# SparkFun-ESP8266-WiFi-Shield.net
KiCad netlist of a schematic drawn in EAGLE
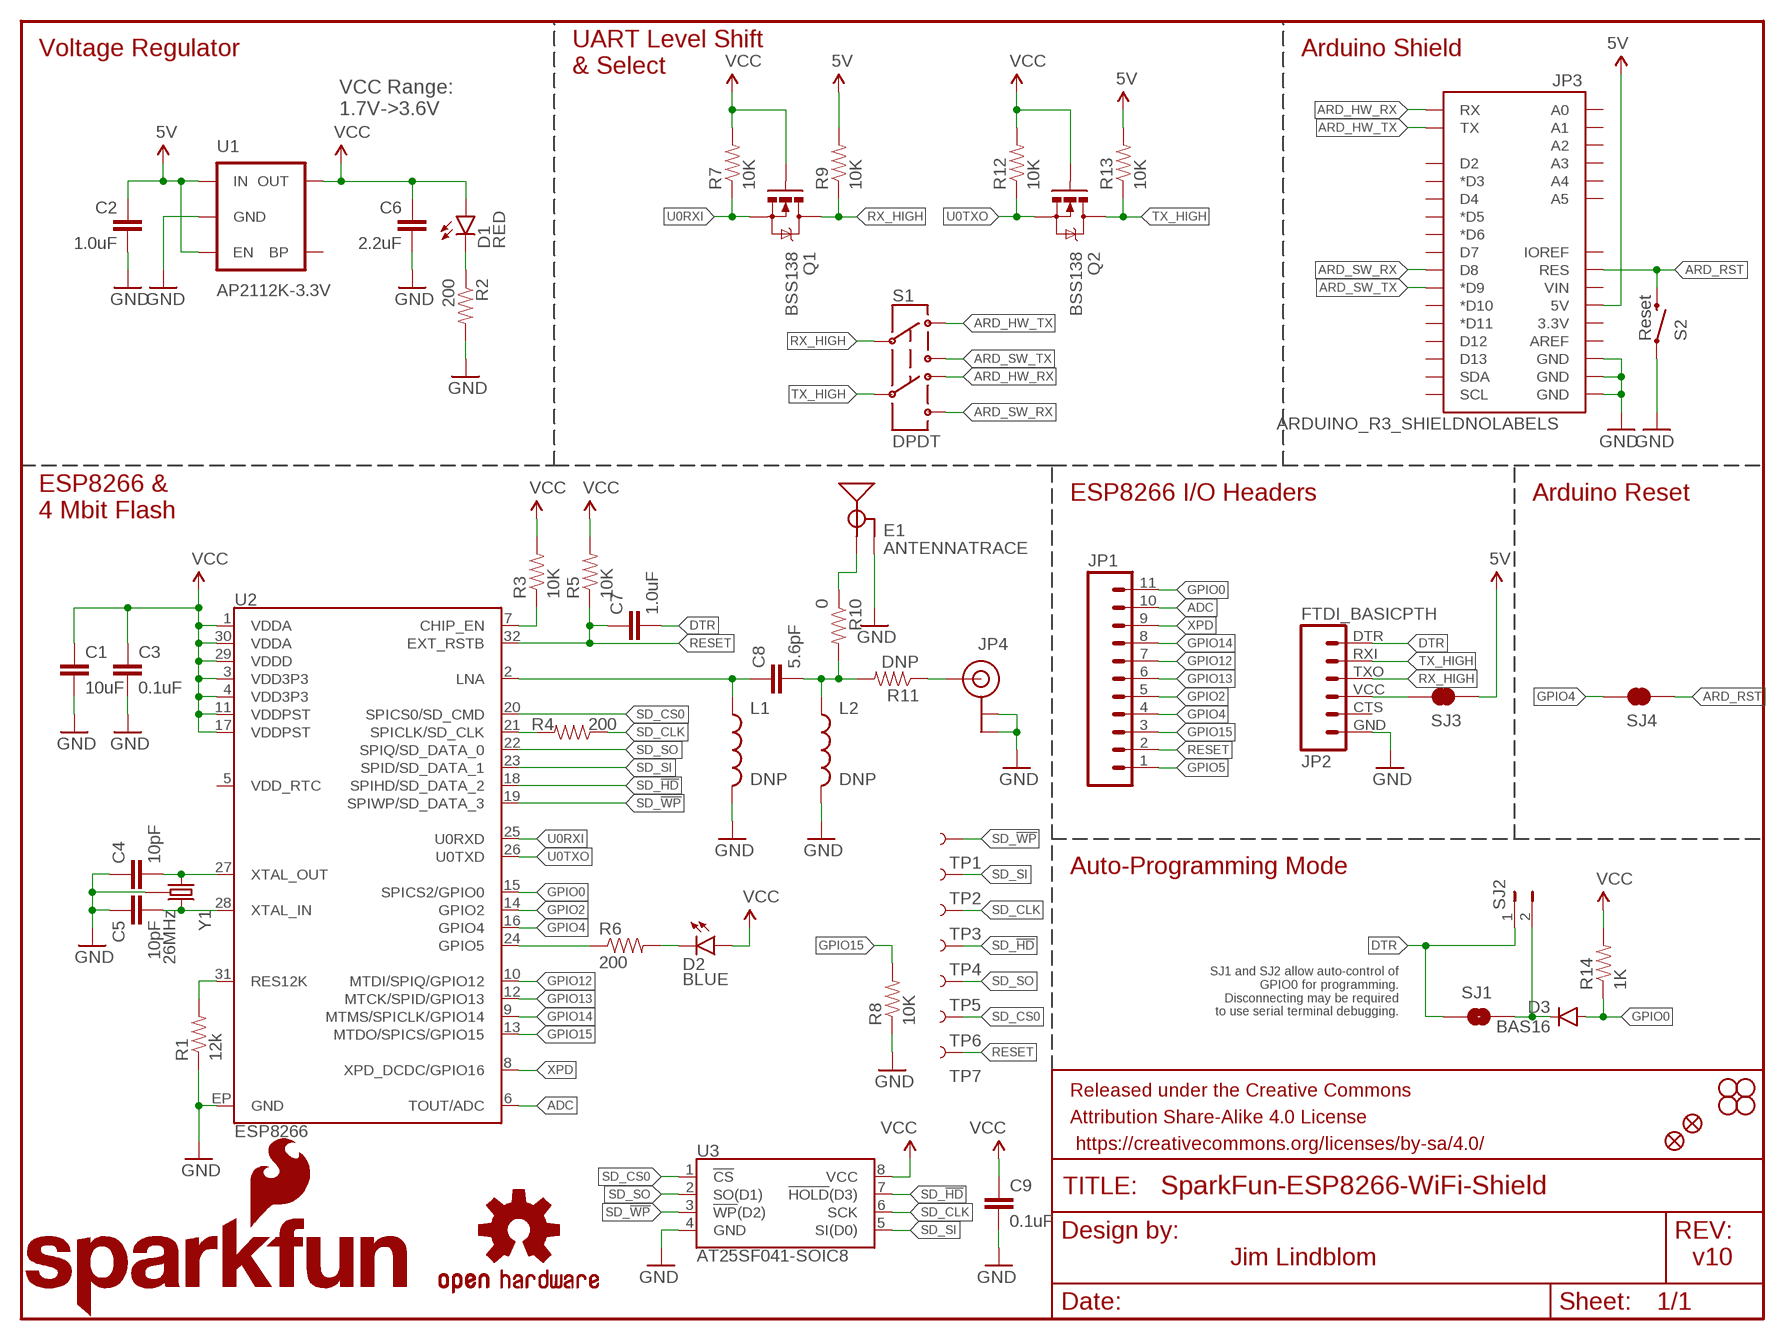
[diagram p0: schematic, sheet 1]

(export (version "E")
  (design (tool "Eeschema 10.0.6"))
  (components
    (comp (ref "C1")
      (value "10uF")
      (footprint "eagle-import:0603-CAP")
      (libsource (lib "eagle-import") (part "10UF-6.3V-20%(0603)"))
    )
    (comp (ref "C2")
      (value "1.0uF")
      (footprint "eagle-import:0805")
      (libsource (lib "eagle-import") (part "1.0UF-25V-+80/-20(0805)"))
    )
    (comp (ref "C3")
      (value "0.1uF")
      (footprint "eagle-import:0603-CAP")
      (libsource (lib "eagle-import") (part "0.1UF-25V(+80/-20%)(0603)"))
    )
    (comp (ref "C4")
      (value "10pF")
      (footprint "eagle-import:0603-CAP")
      (libsource (lib "eagle-import") (part "10PF-50V-5%(0603)"))
    )
    (comp (ref "C5")
      (value "10pF")
      (footprint "eagle-import:0603-CAP")
      (libsource (lib "eagle-import") (part "10PF-50V-5%(0603)"))
    )
    (comp (ref "C6")
      (value "2.2uF")
      (footprint "eagle-import:0603-CAP")
      (libsource (lib "eagle-import") (part "2.2UF-10V-20%(0603)"))
    )
    (comp (ref "C7")
      (value "1.0uF")
      (footprint "eagle-import:0603-CAP")
      (libsource (lib "eagle-import") (part "1.0UF-16V-10%(0603)"))
    )
    (comp (ref "C8")
      (value "5.6pF")
      (footprint "eagle-import:0603-CAP")
      (libsource (lib "eagle-import") (part "CAP0603-CAP"))
    )
    (comp (ref "C9")
      (value "0.1uF")
      (footprint "eagle-import:0603-CAP")
      (libsource (lib "eagle-import") (part "0.1UF-25V(+80/-20%)(0603)"))
    )
    (comp (ref "D1")
      (value "RED")
      (footprint "eagle-import:LED-0603")
      (libsource (lib "eagle-import") (part "LED-RED0603"))
    )
    (comp (ref "D2")
      (value "BLUE")
      (footprint "eagle-import:LED-0603")
      (libsource (lib "eagle-import") (part "LED-BLUE0603"))
    )
    (comp (ref "D3")
      (value "BAS16")
      (footprint "eagle-import:SOD-323")
      (libsource (lib "eagle-import") (part "DIODEBAS16"))
    )
    (comp (ref "E1")
      (value "ANTENNATRACE")
      (footprint "eagle-import:TRACE_ANTENNA_2.4GHZ_25.7MM")
      (libsource (lib "eagle-import") (part "ANTENNATRACE"))
    )
    (comp (ref "FID1")
      (value "FIDUCIAL1X2")
      (footprint "eagle-import:FIDUCIAL-1X2")
      (libsource (lib "eagle-import") (part "FIDUCIAL1X2"))
    )
    (comp (ref "FID2")
      (value "FIDUCIAL1X2")
      (footprint "eagle-import:FIDUCIAL-1X2")
      (libsource (lib "eagle-import") (part "FIDUCIAL1X2"))
    )
    (comp (ref "FRAME1")
      (value "FRAME-LETTER")
      (footprint "eagle-import:CREATIVE_COMMONS")
      (fields (field (name "DESIGNER") "Jim Lindblom"))
      (libsource (lib "eagle-import") (part "FRAME-LETTER"))
    )
    (comp (ref "JP1")
      (value "M11PTH")
      (footprint "eagle-import:1X11")
      (libsource (lib "eagle-import") (part "M11PTH"))
    )
    (comp (ref "JP2")
      (value "FTDI_BASICPTH")
      (footprint "eagle-import:FTDI_BASIC")
      (libsource (lib "eagle-import") (part "FTDI_BASICPTH"))
    )
    (comp (ref "JP3")
      (value "ARDUINO_R3_SHIELDNOLABELS")
      (footprint "eagle-import:UNO_R3_SHIELD_NOLABELS")
      (libsource (lib "eagle-import") (part "ARDUINO_R3_SHIELDNOLABELS"))
    )
    (comp (ref "JP4")
      (value "U.FL")
      (footprint "eagle-import:U.FL")
      (libsource (lib "eagle-import") (part "U.FL"))
    )
    (comp (ref "L1")
      (value "DNP")
      (footprint "eagle-import:0603")
      (libsource (lib "eagle-import") (part "INDUCTOR0603"))
    )
    (comp (ref "L2")
      (value "DNP")
      (footprint "eagle-import:0603")
      (libsource (lib "eagle-import") (part "INDUCTOR0603"))
    )
    (comp (ref "LOGO1")
      (value "SFE_LOGO_NAME_FLAME.2_INCH")
      (footprint "eagle-import:SFE_LOGO_NAME_FLAME_.2")
      (libsource (lib "eagle-import") (part "SFE_LOGO_NAME_FLAME.2_INCH"))
    )
    (comp (ref "LOGO2")
      (value "OSHW-LOGOM")
      (footprint "eagle-import:OSHW-LOGO-M")
      (libsource (lib "eagle-import") (part "OSHW-LOGOM"))
    )
    (comp (ref "Q1")
      (value "BSS138")
      (footprint "eagle-import:SOT23-3")
      (libsource (lib "eagle-import") (part "MOSFET-NCHANNELBSS138"))
    )
    (comp (ref "Q2")
      (value "BSS138")
      (footprint "eagle-import:SOT23-3")
      (libsource (lib "eagle-import") (part "MOSFET-NCHANNELBSS138"))
    )
    (comp (ref "R1")
      (value "12k")
      (footprint "eagle-import:0603-RES")
      (libsource (lib "eagle-import") (part "12KOHM-1/10W-1%(0603)"))
    )
    (comp (ref "R2")
      (value "200")
      (footprint "eagle-import:0603-RES")
      (libsource (lib "eagle-import") (part "200OHM1/10W1%(0603)"))
    )
    (comp (ref "R3")
      (value "10K")
      (footprint "eagle-import:0603-RES")
      (libsource (lib "eagle-import") (part "10KOHM1/10W1%(0603)0603"))
    )
    (comp (ref "R4")
      (value "200")
      (footprint "eagle-import:0603-RES")
      (libsource (lib "eagle-import") (part "200OHM1/10W1%(0603)"))
    )
    (comp (ref "R5")
      (value "10K")
      (footprint "eagle-import:0603-RES")
      (libsource (lib "eagle-import") (part "10KOHM1/10W1%(0603)0603"))
    )
    (comp (ref "R6")
      (value "200")
      (footprint "eagle-import:0603-RES")
      (libsource (lib "eagle-import") (part "200OHM1/10W1%(0603)"))
    )
    (comp (ref "R7")
      (value "10K")
      (footprint "eagle-import:0603-RES")
      (libsource (lib "eagle-import") (part "10KOHM1/10W1%(0603)0603"))
    )
    (comp (ref "R8")
      (value "10K")
      (footprint "eagle-import:0603-RES")
      (libsource (lib "eagle-import") (part "10KOHM1/10W1%(0603)0603"))
    )
    (comp (ref "R9")
      (value "10K")
      (footprint "eagle-import:0603-RES")
      (libsource (lib "eagle-import") (part "10KOHM1/10W1%(0603)0603"))
    )
    (comp (ref "R10")
      (value "0")
      (footprint "eagle-import:0603")
      (libsource (lib "eagle-import") (part "0OHM1/10W5%(0603)"))
    )
    (comp (ref "R11")
      (value "DNP")
      (footprint "eagle-import:0603-RES")
      (libsource (lib "eagle-import") (part "RESISTOR0603-RES"))
    )
    (comp (ref "R12")
      (value "10K")
      (footprint "eagle-import:0603-RES")
      (libsource (lib "eagle-import") (part "10KOHM1/10W1%(0603)0603"))
    )
    (comp (ref "R13")
      (value "10K")
      (footprint "eagle-import:0603-RES")
      (libsource (lib "eagle-import") (part "10KOHM1/10W1%(0603)0603"))
    )
    (comp (ref "R14")
      (value "1K")
      (footprint "eagle-import:0603-RES")
      (libsource (lib "eagle-import") (part "1KOHM1/10W1%(0603)"))
    )
    (comp (ref "S1")
      (value "DPDT")
      (footprint "eagle-import:AYZ0202")
      (libsource (lib "eagle-import") (part "SWITCH-DPDTAYZ0202"))
    )
    (comp (ref "S2")
      (value "Reset")
      (footprint "eagle-import:TACTILE-SWITCH-SMD")
      (libsource (lib "eagle-import") (part "SWITCH-MOMENTARY-2SMD"))
    )
    (comp (ref "SJ1")
      (value "JUMPER-PAD-2-NO")
      (footprint "eagle-import:PAD-JUMPER-2-NO_NO_SILK")
      (libsource (lib "eagle-import") (part "JUMPER-PAD-2-NO"))
    )
    (comp (ref "SJ2")
      (value "JUMPER-PTH-2-NO")
      (footprint "eagle-import:PTH-JUMPER-2-NO_NO_SILK")
      (libsource (lib "eagle-import") (part "JUMPER-PTH-2-NO"))
    )
    (comp (ref "SJ3")
      (value "JUMPER-PAD-2-NC_BY_TRACE")
      (footprint "eagle-import:PAD-JUMPER-2-NC_BY_TRACE_YES_SILK")
      (libsource (lib "eagle-import") (part "JUMPER-PAD-2-NC_BY_TRACE"))
    )
    (comp (ref "SJ4")
      (value "JUMPER-PAD-2-NC_BY_TRACE")
      (footprint "eagle-import:PAD-JUMPER-2-NC_BY_TRACE_YES_SILK")
      (libsource (lib "eagle-import") (part "JUMPER-PAD-2-NC_BY_TRACE"))
    )
    (comp (ref "STANDOFF1")
      (value "STAND-OFF")
      (footprint "eagle-import:STAND-OFF")
      (libsource (lib "eagle-import") (part "STAND-OFF"))
    )
    (comp (ref "STANDOFF2")
      (value "STAND-OFF")
      (footprint "eagle-import:STAND-OFF")
      (libsource (lib "eagle-import") (part "STAND-OFF"))
    )
    (comp (ref "STANDOFF3")
      (value "STAND-OFF")
      (footprint "eagle-import:STAND-OFF")
      (libsource (lib "eagle-import") (part "STAND-OFF"))
    )
    (comp (ref "STANDOFF4")
      (value "STAND-OFF")
      (footprint "eagle-import:STAND-OFF")
      (libsource (lib "eagle-import") (part "STAND-OFF"))
    )
    (comp (ref "TP1")
      (value "TEST-POINT3X5")
      (footprint "eagle-import:PAD.03X.05")
      (libsource (lib "eagle-import") (part "TEST-POINT3X5"))
    )
    (comp (ref "TP2")
      (value "TEST-POINT3X5")
      (footprint "eagle-import:PAD.03X.05")
      (libsource (lib "eagle-import") (part "TEST-POINT3X5"))
    )
    (comp (ref "TP3")
      (value "TEST-POINT3X5")
      (footprint "eagle-import:PAD.03X.05")
      (libsource (lib "eagle-import") (part "TEST-POINT3X5"))
    )
    (comp (ref "TP4")
      (value "TEST-POINT3X5")
      (footprint "eagle-import:PAD.03X.05")
      (libsource (lib "eagle-import") (part "TEST-POINT3X5"))
    )
    (comp (ref "TP5")
      (value "TEST-POINT3X5")
      (footprint "eagle-import:PAD.03X.05")
      (libsource (lib "eagle-import") (part "TEST-POINT3X5"))
    )
    (comp (ref "TP6")
      (value "TEST-POINT3X5")
      (footprint "eagle-import:PAD.03X.05")
      (libsource (lib "eagle-import") (part "TEST-POINT3X5"))
    )
    (comp (ref "TP7")
      (value "TEST-POINT3X5")
      (footprint "eagle-import:PAD.03X.05")
      (libsource (lib "eagle-import") (part "TEST-POINT3X5"))
    )
    (comp (ref "U1")
      (value "AP2112K-3.3V")
      (footprint "eagle-import:SOT23-5")
      (libsource (lib "eagle-import") (part "V_REG_LDOSMD"))
    )
    (comp (ref "U2")
      (value "ESP8266")
      (footprint "eagle-import:QFN32")
      (libsource (lib "eagle-import") (part "ESP8266"))
    )
    (comp (ref "U3")
      (value "AT25SF041-SOIC8")
      (footprint "eagle-import:SO08")
      (libsource (lib "eagle-import") (part "AT25SF041-SOIC8"))
    )
    (comp (ref "Y1")
      (value "26MHz")
      (footprint "eagle-import:CRYSTAL-SMD-3.2X2.5")
      (libsource (lib "eagle-import") (part "CRYSTAL-GROUNDED3.2X2.5"))
    )
  )
  (nets
    (net (code "1") (name "/SD_~{HD}") (class "Default")
      (node (ref "TP4") (pin "P$1") (pinfunction "1_P$1") (pintype "bidirectional"))
      (node (ref "U2") (pin "18") (pinfunction "SPIHD/SD_DATA_2_18") (pintype "bidirectional"))
      (node (ref "U3") (pin "7") (pinfunction "~{HOLD}(D3)_7") (pintype "bidirectional"))
    )
    (net (code "2") (name "/SD_~{WP}") (class "Default")
      (node (ref "TP1") (pin "P$1") (pinfunction "1_P$1") (pintype "bidirectional"))
      (node (ref "U2") (pin "19") (pinfunction "SPIWP/SD_DATA_3_19") (pintype "bidirectional"))
      (node (ref "U3") (pin "3") (pinfunction "~{WP}(D2)_3") (pintype "bidirectional"))
    )
    (net (code "3") (name "5V") (class "Default")
      (node (ref "C2") (pin "1") (pinfunction "1_1") (pintype "passive"))
      (node (ref "JP3") (pin "5V") (pinfunction "5V_5V") (pintype "bidirectional"))
      (node (ref "R13") (pin "2") (pinfunction "2_2") (pintype "passive"))
      (node (ref "R9") (pin "2") (pinfunction "2_2") (pintype "passive"))
      (node (ref "SJ3") (pin "1") (pinfunction "1_1") (pintype "passive"))
      (node (ref "U1") (pin "1") (pinfunction "IN_1") (pintype "input"))
      (node (ref "U1") (pin "3") (pinfunction "EN_3") (pintype "input"))
    )
    (net (code "4") (name "ADC") (class "Default")
      (node (ref "JP1") (pin "10") (pinfunction "10_10") (pintype "passive"))
      (node (ref "U2") (pin "6") (pinfunction "TOUT/ADC_6") (pintype "bidirectional"))
    )
    (net (code "5") (name "ARD_HW_RX") (class "Default")
      (node (ref "JP3") (pin "RX") (pinfunction "RX_RX") (pintype "bidirectional"))
      (node (ref "S1") (pin "4") (pinfunction "4_4") (pintype "bidirectional"))
    )
    (net (code "6") (name "ARD_HW_TX") (class "Default")
      (node (ref "JP3") (pin "TX") (pinfunction "TX_TX") (pintype "bidirectional"))
      (node (ref "S1") (pin "1") (pinfunction "1_1") (pintype "bidirectional"))
    )
    (net (code "7") (name "ARD_RST") (class "Default")
      (node (ref "JP3") (pin "RES") (pinfunction "RES_RES") (pintype "bidirectional"))
      (node (ref "S2") (pin "3") (pinfunction "2_3") (pintype "passive"))
      (node (ref "SJ4") (pin "1") (pinfunction "1_1") (pintype "passive"))
    )
    (net (code "8") (name "ARD_SW_RX") (class "Default")
      (node (ref "JP3") (pin "D8") (pinfunction "D8_D8") (pintype "bidirectional"))
      (node (ref "S1") (pin "6") (pinfunction "6_6") (pintype "bidirectional"))
    )
    (net (code "9") (name "ARD_SW_TX") (class "Default")
      (node (ref "JP3") (pin "D9") (pinfunction "*D9_D9") (pintype "bidirectional"))
      (node (ref "S1") (pin "3") (pinfunction "3_3") (pintype "bidirectional"))
    )
    (net (code "10") (name "DTR") (class "Default")
      (node (ref "C7") (pin "2") (pinfunction "2_2") (pintype "passive"))
      (node (ref "JP2") (pin "DTR") (pinfunction "1_DTR") (pintype "passive"))
      (node (ref "SJ1") (pin "1") (pinfunction "1_1") (pintype "passive"))
      (node (ref "SJ2") (pin "1") (pinfunction "1_1") (pintype "passive"))
    )
    (net (code "11") (name "GND") (class "Default")
      (node (ref "C1") (pin "2") (pinfunction "2_2") (pintype "passive"))
      (node (ref "C2") (pin "2") (pinfunction "2_2") (pintype "passive"))
      (node (ref "C3") (pin "2") (pinfunction "2_2") (pintype "passive"))
      (node (ref "C4") (pin "1") (pinfunction "1_1") (pintype "passive"))
      (node (ref "C5") (pin "1") (pinfunction "1_1") (pintype "passive"))
      (node (ref "C6") (pin "2") (pinfunction "2_2") (pintype "passive"))
      (node (ref "C9") (pin "2") (pinfunction "2_2") (pintype "passive"))
      (node (ref "E1") (pin "GND") (pinfunction "GND_GND") (pintype "bidirectional"))
      (node (ref "E1") (pin "GND2") (pinfunction "GND_GND2") (pintype "bidirectional"))
      (node (ref "JP2") (pin "GND") (pinfunction "6_GND") (pintype "passive"))
      (node (ref "JP3") (pin "GND@0") (pinfunction "GND_GND@0") (pintype "bidirectional"))
      (node (ref "JP3") (pin "GND@1") (pinfunction "GND_GND@1") (pintype "bidirectional"))
      (node (ref "JP3") (pin "GND@2") (pinfunction "GND_GND@2") (pintype "bidirectional"))
      (node (ref "JP4") (pin "P$1") (pinfunction "GND_P$1") (pintype "bidirectional"))
      (node (ref "JP4") (pin "P$2") (pinfunction "GND_P$2") (pintype "bidirectional"))
      (node (ref "L1") (pin "2") (pinfunction "2_2") (pintype "passive"))
      (node (ref "L2") (pin "2") (pinfunction "2_2") (pintype "passive"))
      (node (ref "R1") (pin "1") (pinfunction "1_1") (pintype "passive"))
      (node (ref "R2") (pin "2") (pinfunction "2_2") (pintype "passive"))
      (node (ref "R8") (pin "1") (pinfunction "1_1") (pintype "passive"))
      (node (ref "S2") (pin "1") (pinfunction "1_1") (pintype "passive"))
      (node (ref "U1") (pin "2") (pinfunction "GND_2") (pintype "input"))
      (node (ref "U2") (pin "EP") (pinfunction "GND_EP") (pintype "bidirectional"))
      (node (ref "U3") (pin "4") (pinfunction "GND_4") (pintype "bidirectional"))
      (node (ref "Y1") (pin "2") (pinfunction "GND_2") (pintype "passive"))
      (node (ref "Y1") (pin "4") (pinfunction "GND_4") (pintype "passive"))
    )
    (net (code "12") (name "GPIO0") (class "Default")
      (node (ref "D3") (pin "A") (pinfunction "A_A") (pintype "passive"))
      (node (ref "JP1") (pin "11") (pinfunction "11_11") (pintype "passive"))
      (node (ref "R14") (pin "1") (pinfunction "1_1") (pintype "passive"))
      (node (ref "U2") (pin "15") (pinfunction "SPICS2/GPIO0_15") (pintype "bidirectional"))
    )
    (net (code "13") (name "GPIO2") (class "Default")
      (node (ref "JP1") (pin "5") (pinfunction "5_5") (pintype "passive"))
      (node (ref "U2") (pin "14") (pinfunction "GPIO2_14") (pintype "bidirectional"))
    )
    (net (code "14") (name "GPIO4") (class "Default")
      (node (ref "JP1") (pin "4") (pinfunction "4_4") (pintype "passive"))
      (node (ref "SJ4") (pin "2") (pinfunction "2_2") (pintype "passive"))
      (node (ref "U2") (pin "16") (pinfunction "GPIO4_16") (pintype "bidirectional"))
    )
    (net (code "15") (name "GPIO5") (class "Default")
      (node (ref "JP1") (pin "1") (pinfunction "1_1") (pintype "passive"))
      (node (ref "R6") (pin "1") (pinfunction "1_1") (pintype "passive"))
      (node (ref "U2") (pin "24") (pinfunction "GPIO5_24") (pintype "bidirectional"))
    )
    (net (code "16") (name "GPIO12") (class "Default")
      (node (ref "JP1") (pin "7") (pinfunction "7_7") (pintype "passive"))
      (node (ref "U2") (pin "10") (pinfunction "MTDI/SPIQ/GPIO12_10") (pintype "bidirectional"))
    )
    (net (code "17") (name "GPIO13") (class "Default")
      (node (ref "JP1") (pin "6") (pinfunction "6_6") (pintype "passive"))
      (node (ref "U2") (pin "12") (pinfunction "MTCK/SPID/GPIO13_12") (pintype "bidirectional"))
    )
    (net (code "18") (name "GPIO14") (class "Default")
      (node (ref "JP1") (pin "8") (pinfunction "8_8") (pintype "passive"))
      (node (ref "U2") (pin "9") (pinfunction "MTMS/SPICLK/GPIO14_9") (pintype "bidirectional"))
    )
    (net (code "19") (name "GPIO15") (class "Default")
      (node (ref "JP1") (pin "3") (pinfunction "3_3") (pintype "passive"))
      (node (ref "R8") (pin "2") (pinfunction "2_2") (pintype "passive"))
      (node (ref "U2") (pin "13") (pinfunction "MTDO/SPICS/GPIO15_13") (pintype "bidirectional"))
    )
    (net (code "20") (name "Net-(C8-Pad2)") (class "Default")
      (node (ref "C8") (pin "2") (pinfunction "2_2") (pintype "passive"))
      (node (ref "L2") (pin "1") (pinfunction "1_1") (pintype "passive"))
      (node (ref "R10") (pin "2") (pinfunction "2_2") (pintype "passive"))
      (node (ref "R11") (pin "2") (pinfunction "2_2") (pintype "passive"))
    )
    (net (code "21") (name "Net-(D1-PadC)") (class "Default")
      (node (ref "D1") (pin "C") (pinfunction "C_C") (pintype "passive"))
      (node (ref "R2") (pin "1") (pinfunction "1_1") (pintype "passive"))
    )
    (net (code "22") (name "Net-(D2-PadC)") (class "Default")
      (node (ref "D2") (pin "C") (pinfunction "C_C") (pintype "passive"))
      (node (ref "R6") (pin "2") (pinfunction "2_2") (pintype "passive"))
    )
    (net (code "23") (name "Net-(D3-PadC)") (class "Default")
      (node (ref "D3") (pin "C") (pinfunction "C_C") (pintype "passive"))
      (node (ref "SJ1") (pin "2") (pinfunction "2_2") (pintype "passive"))
      (node (ref "SJ2") (pin "2") (pinfunction "2_2") (pintype "passive"))
    )
    (net (code "24") (name "Net-(E1-SIGNAL)") (class "Default")
      (node (ref "E1") (pin "ANT") (pinfunction "SIGNAL_ANT") (pintype "bidirectional"))
      (node (ref "R10") (pin "1") (pinfunction "1_1") (pintype "passive"))
    )
    (net (code "25") (name "Net-(JP2-4)") (class "Default")
      (node (ref "JP2") (pin "VCC") (pinfunction "4_VCC") (pintype "passive"))
      (node (ref "SJ3") (pin "2") (pinfunction "2_2") (pintype "passive"))
    )
    (net (code "26") (name "Net-(JP4-SIGNAL)") (class "Default")
      (node (ref "JP4") (pin "P$3") (pinfunction "SIGNAL_P$3") (pintype "bidirectional"))
      (node (ref "R11") (pin "1") (pinfunction "1_1") (pintype "passive"))
    )
    (net (code "27") (name "Net-(U2-CHIP_EN)") (class "Default")
      (node (ref "R3") (pin "1") (pinfunction "1_1") (pintype "passive"))
      (node (ref "U2") (pin "7") (pinfunction "CHIP_EN_7") (pintype "bidirectional"))
    )
    (net (code "28") (name "Net-(U2-LNA)") (class "Default")
      (node (ref "C8") (pin "1") (pinfunction "1_1") (pintype "passive"))
      (node (ref "L1") (pin "1") (pinfunction "1_1") (pintype "passive"))
      (node (ref "U2") (pin "2") (pinfunction "LNA_2") (pintype "bidirectional"))
    )
    (net (code "29") (name "Net-(U2-RES12K)") (class "Default")
      (node (ref "R1") (pin "2") (pinfunction "2_2") (pintype "passive"))
      (node (ref "U2") (pin "31") (pinfunction "RES12K_31") (pintype "bidirectional"))
    )
    (net (code "30") (name "Net-(U2-SPICLK{slash}SD_CLK)") (class "Default")
      (node (ref "R4") (pin "2") (pinfunction "2_2") (pintype "passive"))
      (node (ref "U2") (pin "21") (pinfunction "SPICLK/SD_CLK_21") (pintype "bidirectional"))
    )
    (net (code "31") (name "Net-(U2-XTAL_IN)") (class "Default")
      (node (ref "C5") (pin "2") (pinfunction "2_2") (pintype "passive"))
      (node (ref "U2") (pin "28") (pinfunction "XTAL_IN_28") (pintype "bidirectional"))
      (node (ref "Y1") (pin "3") (pinfunction "2_3") (pintype "passive"))
    )
    (net (code "32") (name "Net-(U2-XTAL_OUT)") (class "Default")
      (node (ref "C4") (pin "2") (pinfunction "2_2") (pintype "passive"))
      (node (ref "U2") (pin "27") (pinfunction "XTAL_OUT_27") (pintype "bidirectional"))
      (node (ref "Y1") (pin "1") (pinfunction "1_1") (pintype "passive"))
    )
    (net (code "33") (name "RESET") (class "Default")
      (node (ref "C7") (pin "1") (pinfunction "1_1") (pintype "passive"))
      (node (ref "JP1") (pin "2") (pinfunction "2_2") (pintype "passive"))
      (node (ref "R5") (pin "1") (pinfunction "1_1") (pintype "passive"))
      (node (ref "TP7") (pin "P$1") (pinfunction "1_P$1") (pintype "bidirectional"))
      (node (ref "U2") (pin "32") (pinfunction "EXT_RSTB_32") (pintype "bidirectional"))
    )
    (net (code "34") (name "RX_HIGH") (class "Default")
      (node (ref "JP2") (pin "TXO") (pinfunction "3_TXO") (pintype "passive"))
      (node (ref "Q1") (pin "3") (pinfunction "D_3") (pintype "passive"))
      (node (ref "R9") (pin "1") (pinfunction "1_1") (pintype "passive"))
      (node (ref "S1") (pin "2") (pinfunction "2_2") (pintype "bidirectional"))
    )
    (net (code "35") (name "SD_CLK") (class "Default")
      (node (ref "R4") (pin "1") (pinfunction "1_1") (pintype "passive"))
      (node (ref "TP3") (pin "P$1") (pinfunction "1_P$1") (pintype "bidirectional"))
      (node (ref "U3") (pin "6") (pinfunction "SCK_6") (pintype "bidirectional"))
    )
    (net (code "36") (name "SD_CS0") (class "Default")
      (node (ref "TP6") (pin "P$1") (pinfunction "1_P$1") (pintype "bidirectional"))
      (node (ref "U2") (pin "20") (pinfunction "SPICS0/SD_CMD_20") (pintype "bidirectional"))
      (node (ref "U3") (pin "1") (pinfunction "~{CS}_1") (pintype "bidirectional"))
    )
    (net (code "37") (name "SD_SI") (class "Default")
      (node (ref "TP2") (pin "P$1") (pinfunction "1_P$1") (pintype "bidirectional"))
      (node (ref "U2") (pin "23") (pinfunction "SPID/SD_DATA_1_23") (pintype "bidirectional"))
      (node (ref "U3") (pin "5") (pinfunction "SI(D0)_5") (pintype "bidirectional"))
    )
    (net (code "38") (name "SD_SO") (class "Default")
      (node (ref "TP5") (pin "P$1") (pinfunction "1_P$1") (pintype "bidirectional"))
      (node (ref "U2") (pin "22") (pinfunction "SPIQ/SD_DATA_0_22") (pintype "bidirectional"))
      (node (ref "U3") (pin "2") (pinfunction "SO(D1)_2") (pintype "bidirectional"))
    )
    (net (code "39") (name "TX_HIGH") (class "Default")
      (node (ref "JP2") (pin "RXI") (pinfunction "2_RXI") (pintype "passive"))
      (node (ref "Q2") (pin "3") (pinfunction "D_3") (pintype "passive"))
      (node (ref "R13") (pin "1") (pinfunction "1_1") (pintype "passive"))
      (node (ref "S1") (pin "5") (pinfunction "5_5") (pintype "bidirectional"))
    )
    (net (code "40") (name "U0RXI") (class "Default")
      (node (ref "Q1") (pin "2") (pinfunction "S_2") (pintype "passive"))
      (node (ref "R7") (pin "1") (pinfunction "1_1") (pintype "passive"))
      (node (ref "U2") (pin "25") (pinfunction "U0RXD_25") (pintype "bidirectional"))
    )
    (net (code "41") (name "U0TXO") (class "Default")
      (node (ref "Q2") (pin "2") (pinfunction "S_2") (pintype "passive"))
      (node (ref "R12") (pin "1") (pinfunction "1_1") (pintype "passive"))
      (node (ref "U2") (pin "26") (pinfunction "U0TXD_26") (pintype "bidirectional"))
    )
    (net (code "42") (name "VCC") (class "Default")
      (node (ref "C1") (pin "1") (pinfunction "1_1") (pintype "passive"))
      (node (ref "C3") (pin "1") (pinfunction "1_1") (pintype "passive"))
      (node (ref "C6") (pin "1") (pinfunction "1_1") (pintype "passive"))
      (node (ref "C9") (pin "1") (pinfunction "1_1") (pintype "passive"))
      (node (ref "D1") (pin "A") (pinfunction "A_A") (pintype "passive"))
      (node (ref "D2") (pin "A") (pinfunction "A_A") (pintype "passive"))
      (node (ref "Q1") (pin "1") (pinfunction "G_1") (pintype "passive"))
      (node (ref "Q2") (pin "1") (pinfunction "G_1") (pintype "passive"))
      (node (ref "R12") (pin "2") (pinfunction "2_2") (pintype "passive"))
      (node (ref "R14") (pin "2") (pinfunction "2_2") (pintype "passive"))
      (node (ref "R3") (pin "2") (pinfunction "2_2") (pintype "passive"))
      (node (ref "R5") (pin "2") (pinfunction "2_2") (pintype "passive"))
      (node (ref "R7") (pin "2") (pinfunction "2_2") (pintype "passive"))
      (node (ref "U1") (pin "5") (pinfunction "OUT_5") (pintype "passive"))
      (node (ref "U2") (pin "1") (pinfunction "VDDA_1") (pintype "bidirectional"))
      (node (ref "U2") (pin "11") (pinfunction "VDDPST_11") (pintype "bidirectional"))
      (node (ref "U2") (pin "17") (pinfunction "VDDPST_17") (pintype "bidirectional"))
      (node (ref "U2") (pin "29") (pinfunction "VDDD_29") (pintype "bidirectional"))
      (node (ref "U2") (pin "3") (pinfunction "VDD3P3_3") (pintype "bidirectional"))
      (node (ref "U2") (pin "30") (pinfunction "VDDA_30") (pintype "bidirectional"))
      (node (ref "U2") (pin "4") (pinfunction "VDD3P3_4") (pintype "bidirectional"))
      (node (ref "U3") (pin "8") (pinfunction "VCC_8") (pintype "bidirectional"))
    )
    (net (code "43") (name "XPD") (class "Default")
      (node (ref "JP1") (pin "9") (pinfunction "9_9") (pintype "passive"))
      (node (ref "U2") (pin "8") (pinfunction "XPD_DCDC/GPIO16_8") (pintype "bidirectional"))
    )
    (net (code "44") (name "unconnected-(JP2-5-PadCTS)") (class "Default")
      (node (ref "JP2") (pin "CTS") (pinfunction "5_CTS") (pintype "passive"))
    )
    (net (code "45") (name "unconnected-(JP3-*D3-PadD3)") (class "Default")
      (node (ref "JP3") (pin "D3") (pinfunction "*D3_D3") (pintype "bidirectional"))
    )
    (net (code "46") (name "unconnected-(JP3-*D5-PadD5)") (class "Default")
      (node (ref "JP3") (pin "D5") (pinfunction "*D5_D5") (pintype "bidirectional"))
    )
    (net (code "47") (name "unconnected-(JP3-*D6-PadD6)") (class "Default")
      (node (ref "JP3") (pin "D6") (pinfunction "*D6_D6") (pintype "bidirectional"))
    )
    (net (code "48") (name "unconnected-(JP3-*D10-PadD10)") (class "Default")
      (node (ref "JP3") (pin "D10") (pinfunction "*D10_D10") (pintype "bidirectional"))
    )
    (net (code "49") (name "unconnected-(JP3-*D11-PadD11)") (class "Default")
      (node (ref "JP3") (pin "D11") (pinfunction "*D11_D11") (pintype "bidirectional"))
    )
    (net (code "50") (name "unconnected-(JP3-Pad3.3V)") (class "Default")
      (node (ref "JP3") (pin "3.3V") (pinfunction "3.3V_3.3V") (pintype "bidirectional"))
    )
    (net (code "51") (name "unconnected-(JP3-PadA0)") (class "Default")
      (node (ref "JP3") (pin "A0") (pinfunction "A0_A0") (pintype "bidirectional"))
    )
    (net (code "52") (name "unconnected-(JP3-PadA1)") (class "Default")
      (node (ref "JP3") (pin "A1") (pinfunction "A1_A1") (pintype "bidirectional"))
    )
    (net (code "53") (name "unconnected-(JP3-PadA2)") (class "Default")
      (node (ref "JP3") (pin "A2") (pinfunction "A2_A2") (pintype "bidirectional"))
    )
    (net (code "54") (name "unconnected-(JP3-PadA3)") (class "Default")
      (node (ref "JP3") (pin "A3") (pinfunction "A3_A3") (pintype "bidirectional"))
    )
    (net (code "55") (name "unconnected-(JP3-PadA4)") (class "Default")
      (node (ref "JP3") (pin "A4") (pinfunction "A4_A4") (pintype "bidirectional"))
    )
    (net (code "56") (name "unconnected-(JP3-PadA5)") (class "Default")
      (node (ref "JP3") (pin "A5") (pinfunction "A5_A5") (pintype "bidirectional"))
    )
    (net (code "57") (name "unconnected-(JP3-PadAREF)") (class "Default")
      (node (ref "JP3") (pin "AREF") (pinfunction "AREF_AREF") (pintype "bidirectional"))
    )
    (net (code "58") (name "unconnected-(JP3-PadD2)") (class "Default")
      (node (ref "JP3") (pin "D2") (pinfunction "D2_D2") (pintype "bidirectional"))
    )
    (net (code "59") (name "unconnected-(JP3-PadD4)") (class "Default")
      (node (ref "JP3") (pin "D4") (pinfunction "D4_D4") (pintype "bidirectional"))
    )
    (net (code "60") (name "unconnected-(JP3-PadD7)") (class "Default")
      (node (ref "JP3") (pin "D7") (pinfunction "D7_D7") (pintype "bidirectional"))
    )
    (net (code "61") (name "unconnected-(JP3-PadD12)") (class "Default")
      (node (ref "JP3") (pin "D12") (pinfunction "D12_D12") (pintype "bidirectional"))
    )
    (net (code "62") (name "unconnected-(JP3-PadD13)") (class "Default")
      (node (ref "JP3") (pin "D13") (pinfunction "D13_D13") (pintype "bidirectional"))
    )
    (net (code "63") (name "unconnected-(JP3-PadIOREF)") (class "Default")
      (node (ref "JP3") (pin "IOREF") (pinfunction "IOREF_IOREF") (pintype "bidirectional"))
    )
    (net (code "64") (name "unconnected-(JP3-PadSCL)") (class "Default")
      (node (ref "JP3") (pin "SCL") (pinfunction "SCL_SCL") (pintype "bidirectional"))
    )
    (net (code "65") (name "unconnected-(JP3-PadSDA)") (class "Default")
      (node (ref "JP3") (pin "SDA") (pinfunction "SDA_SDA") (pintype "bidirectional"))
    )
    (net (code "66") (name "unconnected-(JP3-PadVIN)") (class "Default")
      (node (ref "JP3") (pin "VIN") (pinfunction "VIN_VIN") (pintype "bidirectional"))
    )
    (net (code "67") (name "unconnected-(U1-BP-Pad4)") (class "Default")
      (node (ref "U1") (pin "4") (pinfunction "BP_4") (pintype "input"))
    )
    (net (code "68") (name "unconnected-(U2-VDD_RTC-Pad5)") (class "Default")
      (node (ref "U2") (pin "5") (pinfunction "VDD_RTC_5") (pintype "bidirectional"))
    )
  )
)
